# top.net
KiCad netlist of a schematic drawn in Altium Designer
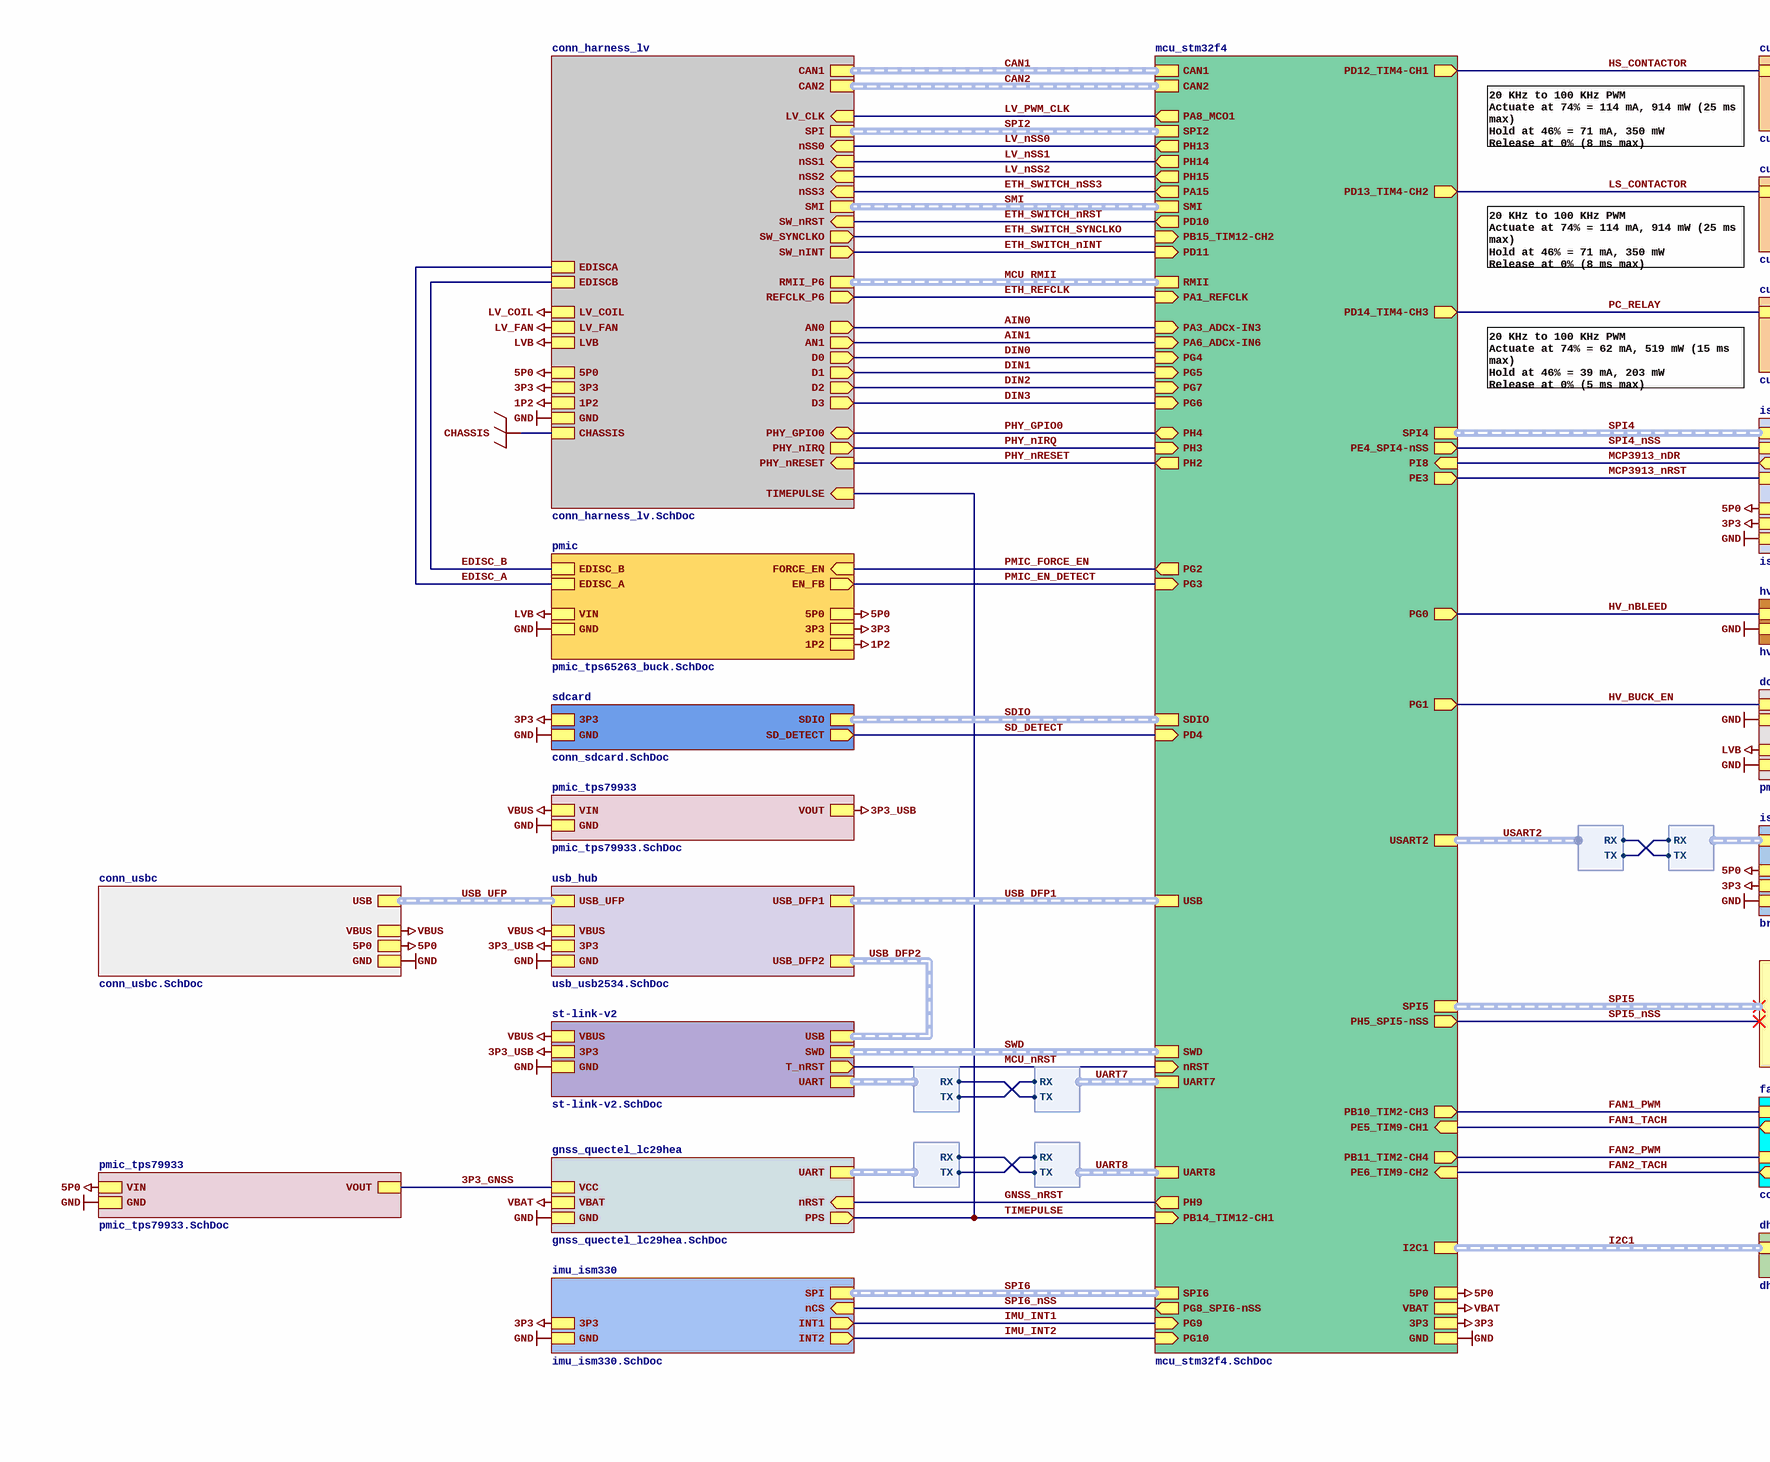
[diagram p0: top.SchDoc, left]
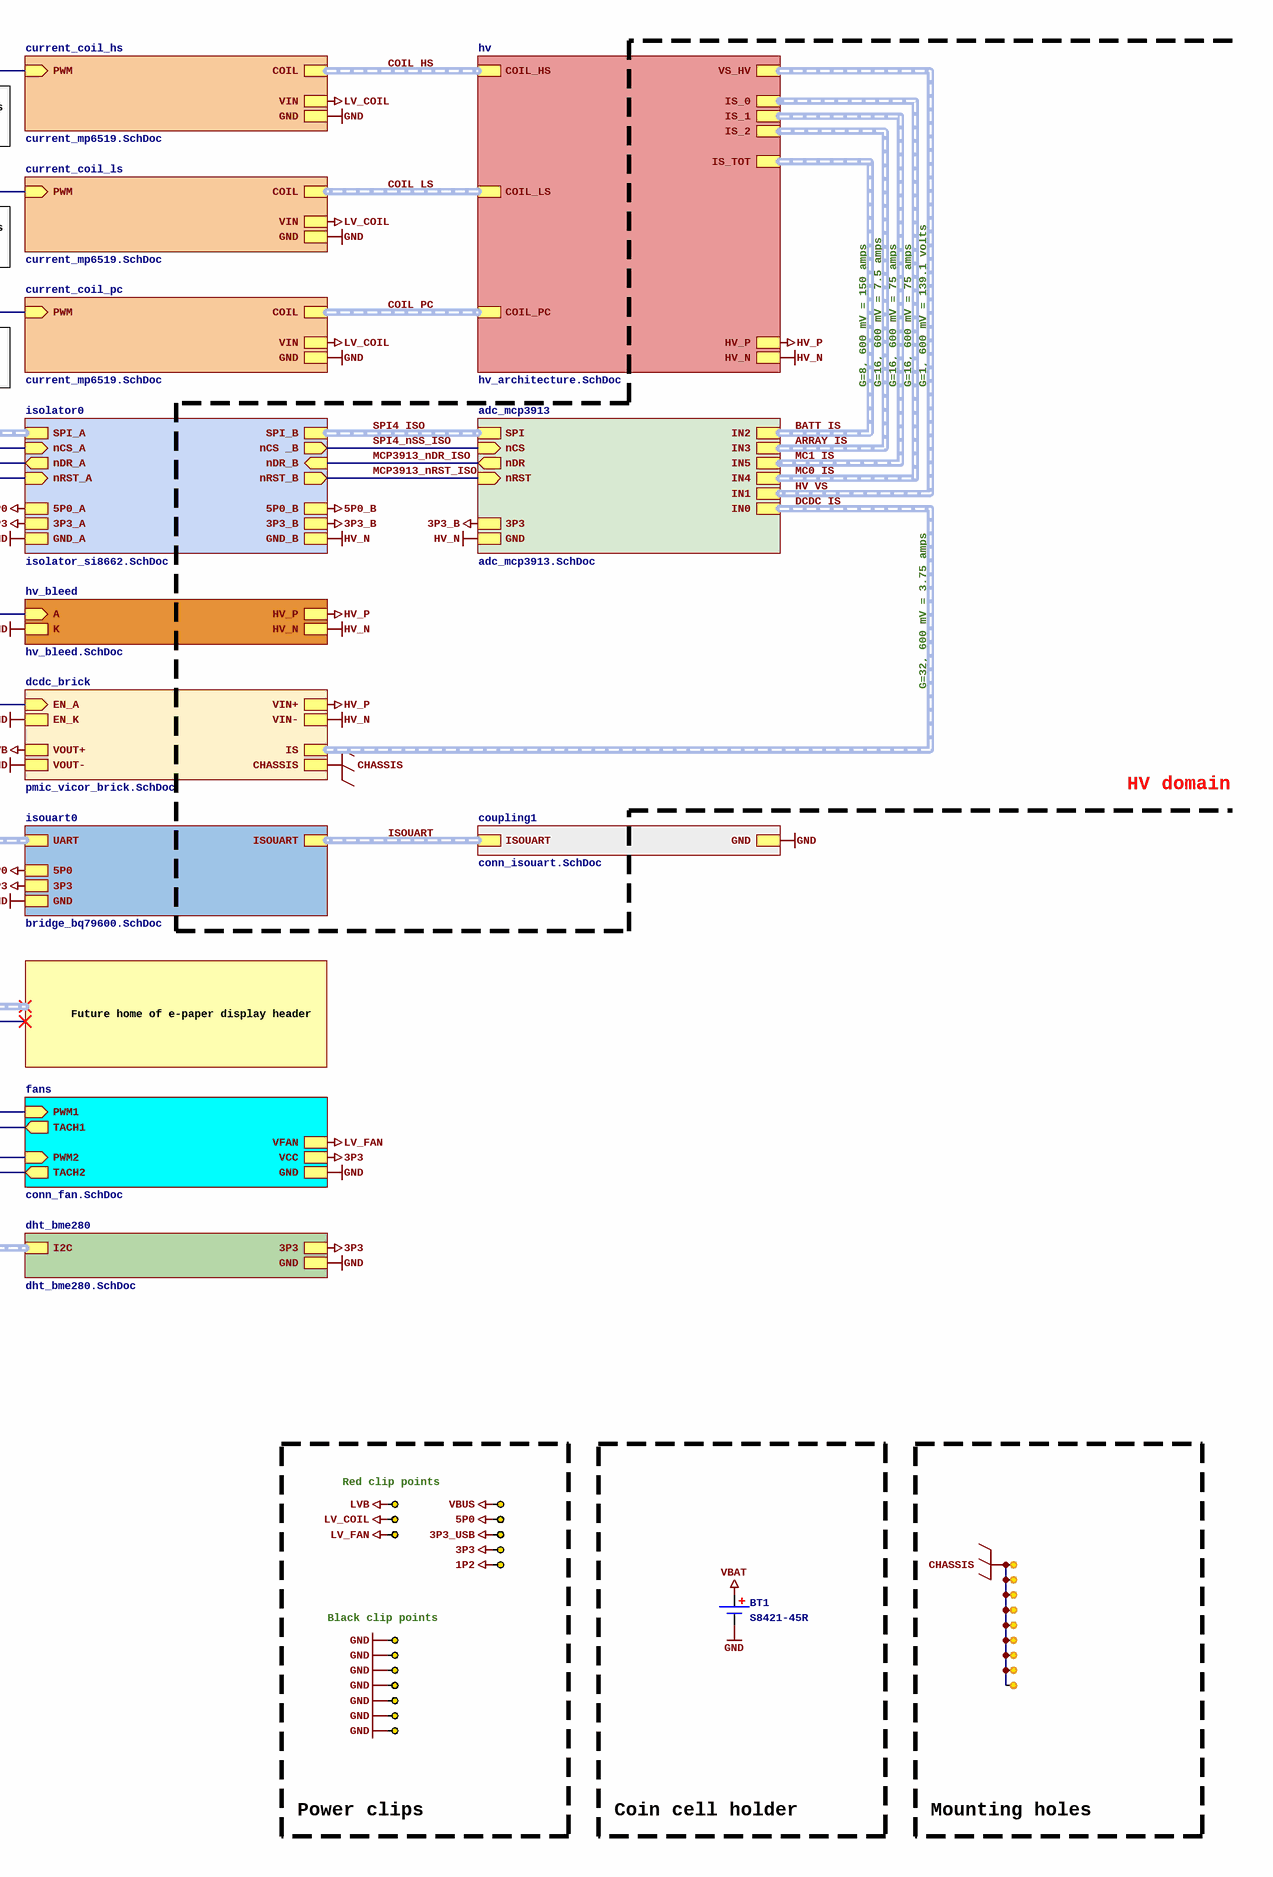
[diagram p1: top.SchDoc, right]

(export (version "E")
  (design (tool "Eeschema 10.0.6"))
  (components
    (comp (ref "BT1")
      (value "S8421-45R")
      (footprint "HOLDER_BATT_CR2032_HARWIN_S8421-45R")
      (description "EZ-Coin Cell Battery Retainer, Horizontal SMT, for CR2032 Coin Cell Batteries")
      (fields (field (name "MANUFACTURER") "Harwin"))
      (libsource (lib "SSCP") (part "HOLDER_BATT_CR2032_HARWIN_S8421-45R"))
    )
    (comp (ref "MH1") (value "HOLE_M3") (footprint "HOLE_M3") (libsource (lib "SSCP") (part "HOLE_M3")))
    (comp (ref "MH2") (value "HOLE_M3") (footprint "HOLE_M3") (libsource (lib "SSCP") (part "HOLE_M3")))
    (comp (ref "MH3") (value "HOLE_M3") (footprint "HOLE_M3") (libsource (lib "SSCP") (part "HOLE_M3")))
    (comp (ref "MH4") (value "HOLE_M3") (footprint "HOLE_M3") (libsource (lib "SSCP") (part "HOLE_M3")))
    (comp (ref "MH5") (value "HOLE_M3") (footprint "HOLE_M3") (libsource (lib "SSCP") (part "HOLE_M3")))
    (comp (ref "MH6") (value "HOLE_M3") (footprint "HOLE_M3") (libsource (lib "SSCP") (part "HOLE_M3")))
    (comp (ref "MH7") (value "HOLE_M3") (footprint "HOLE_M3") (libsource (lib "SSCP") (part "HOLE_M3")))
    (comp (ref "MH8") (value "HOLE_M3") (footprint "HOLE_M3") (libsource (lib "SSCP") (part "HOLE_M3")))
    (comp (ref "MH9") (value "HOLE_M3") (footprint "HOLE_M3") (libsource (lib "SSCP") (part "HOLE_M3")))
    (comp (ref "TP32")
      (value "RH-5000")
      (footprint "TP_RH-5000")
      (fields (field (name "MANUFACTURER") "ronghe"))
      (libsource (lib "database") (part "__template_testpoint"))
    )
    (comp (ref "TP33")
      (value "RH-5000")
      (footprint "TP_RH-5000")
      (fields (field (name "MANUFACTURER") "ronghe"))
      (libsource (lib "database") (part "__template_testpoint"))
    )
    (comp (ref "TP34")
      (value "RH-5000")
      (footprint "TP_RH-5000")
      (fields (field (name "MANUFACTURER") "ronghe"))
      (libsource (lib "database") (part "__template_testpoint"))
    )
    (comp (ref "TP35")
      (value "RH-5000")
      (footprint "TP_RH-5000")
      (fields (field (name "MANUFACTURER") "ronghe"))
      (libsource (lib "database") (part "__template_testpoint"))
    )
    (comp (ref "TP36")
      (value "RH-5000")
      (footprint "TP_RH-5000")
      (fields (field (name "MANUFACTURER") "ronghe"))
      (libsource (lib "database") (part "__template_testpoint"))
    )
    (comp (ref "TP37")
      (value "RH-5000")
      (footprint "TP_RH-5000")
      (fields (field (name "MANUFACTURER") "ronghe"))
      (libsource (lib "database") (part "__template_testpoint"))
    )
    (comp (ref "TP39")
      (value "RH-5001")
      (footprint "TP_RH-5001")
      (fields (field (name "MANUFACTURER") "ronghe"))
      (libsource (lib "database") (part "__template_testpoint"))
    )
    (comp (ref "TP41")
      (value "RH-5001")
      (footprint "TP_RH-5001")
      (fields (field (name "MANUFACTURER") "ronghe"))
      (libsource (lib "database") (part "__template_testpoint"))
    )
    (comp (ref "TP43")
      (value "RH-5001")
      (footprint "TP_RH-5001")
      (fields (field (name "MANUFACTURER") "ronghe"))
      (libsource (lib "database") (part "__template_testpoint"))
    )
    (comp (ref "TP45")
      (value "RH-5001")
      (footprint "TP_RH-5001")
      (fields (field (name "MANUFACTURER") "ronghe"))
      (libsource (lib "database") (part "__template_testpoint"))
    )
    (comp (ref "TP46")
      (value "RH-5001")
      (footprint "TP_RH-5001")
      (fields (field (name "MANUFACTURER") "ronghe"))
      (libsource (lib "database") (part "__template_testpoint"))
    )
    (comp (ref "TP47")
      (value "RH-5001")
      (footprint "TP_RH-5001")
      (fields (field (name "MANUFACTURER") "ronghe"))
      (libsource (lib "database") (part "__template_testpoint"))
    )
    (comp (ref "TP48")
      (value "RH-5001")
      (footprint "TP_RH-5001")
      (fields (field (name "MANUFACTURER") "ronghe"))
      (libsource (lib "database") (part "__template_testpoint"))
    )
    (comp (ref "TP89")
      (value "RH-5000")
      (footprint "TP_RH-5000")
      (fields (field (name "MANUFACTURER") "ronghe"))
      (libsource (lib "database") (part "__template_testpoint"))
    )
    (comp (ref "TP90")
      (value "RH-5000")
      (footprint "TP_RH-5000")
      (fields (field (name "MANUFACTURER") "ronghe"))
      (libsource (lib "database") (part "__template_testpoint"))
    )
  )
  (nets
    (net (code "105") (name "1P2") (class "Default") (node (ref "TP37") (pin "1") (pintype "passive")))
    (net (code "106") (name "3P3") (class "Default") (node (ref "TP35") (pin "1") (pintype "passive")))
    (net (code "108") (name "3P3_USB") (class "Default") (node (ref "TP90") (pin "1") (pintype "passive")))
    (net (code "109") (name "5P0") (class "Default") (node (ref "TP33") (pin "1") (pintype "passive")))
    (net (code "111") (name "CHASSIS") (class "Default")
      (node (ref "MH1") (pin "0") (pintype "passive"))
      (node (ref "MH2") (pin "0") (pintype "passive"))
      (node (ref "MH3") (pin "0") (pintype "passive"))
      (node (ref "MH4") (pin "0") (pintype "passive"))
      (node (ref "MH5") (pin "0") (pintype "passive"))
      (node (ref "MH6") (pin "0") (pintype "passive"))
      (node (ref "MH7") (pin "0") (pintype "passive"))
      (node (ref "MH8") (pin "0") (pintype "passive"))
      (node (ref "MH9") (pin "0") (pintype "passive"))
    )
    (net (code "112") (name "GND") (class "Default")
      (node (ref "BT1") (pin "2") (pinfunction "-_2") (pintype "passive"))
      (node (ref "TP39") (pin "1") (pintype "passive"))
      (node (ref "TP41") (pin "1") (pintype "passive"))
      (node (ref "TP43") (pin "1") (pintype "passive"))
      (node (ref "TP45") (pin "1") (pintype "passive"))
      (node (ref "TP46") (pin "1") (pintype "passive"))
      (node (ref "TP47") (pin "1") (pintype "passive"))
      (node (ref "TP48") (pin "1") (pintype "passive"))
    )
    (net (code "115") (name "LVB") (class "Default") (node (ref "TP32") (pin "1") (pintype "passive")))
    (net (code "116") (name "LV_COIL") (class "Default") (node (ref "TP34") (pin "1") (pintype "passive")))
    (net (code "117") (name "LV_FAN") (class "Default") (node (ref "TP36") (pin "1") (pintype "passive")))
    (net (code "118") (name "VBAT") (class "Default")
      (node (ref "BT1") (pin "1") (pinfunction "+_1") (pintype "passive"))
    )
    (net (code "119") (name "VBUS") (class "Default") (node (ref "TP89") (pin "1") (pintype "passive")))
  )
)
